# SCH_555-Circuit_2025-12-31.net
KiCad netlist of a schematic drawn in EasyEDA
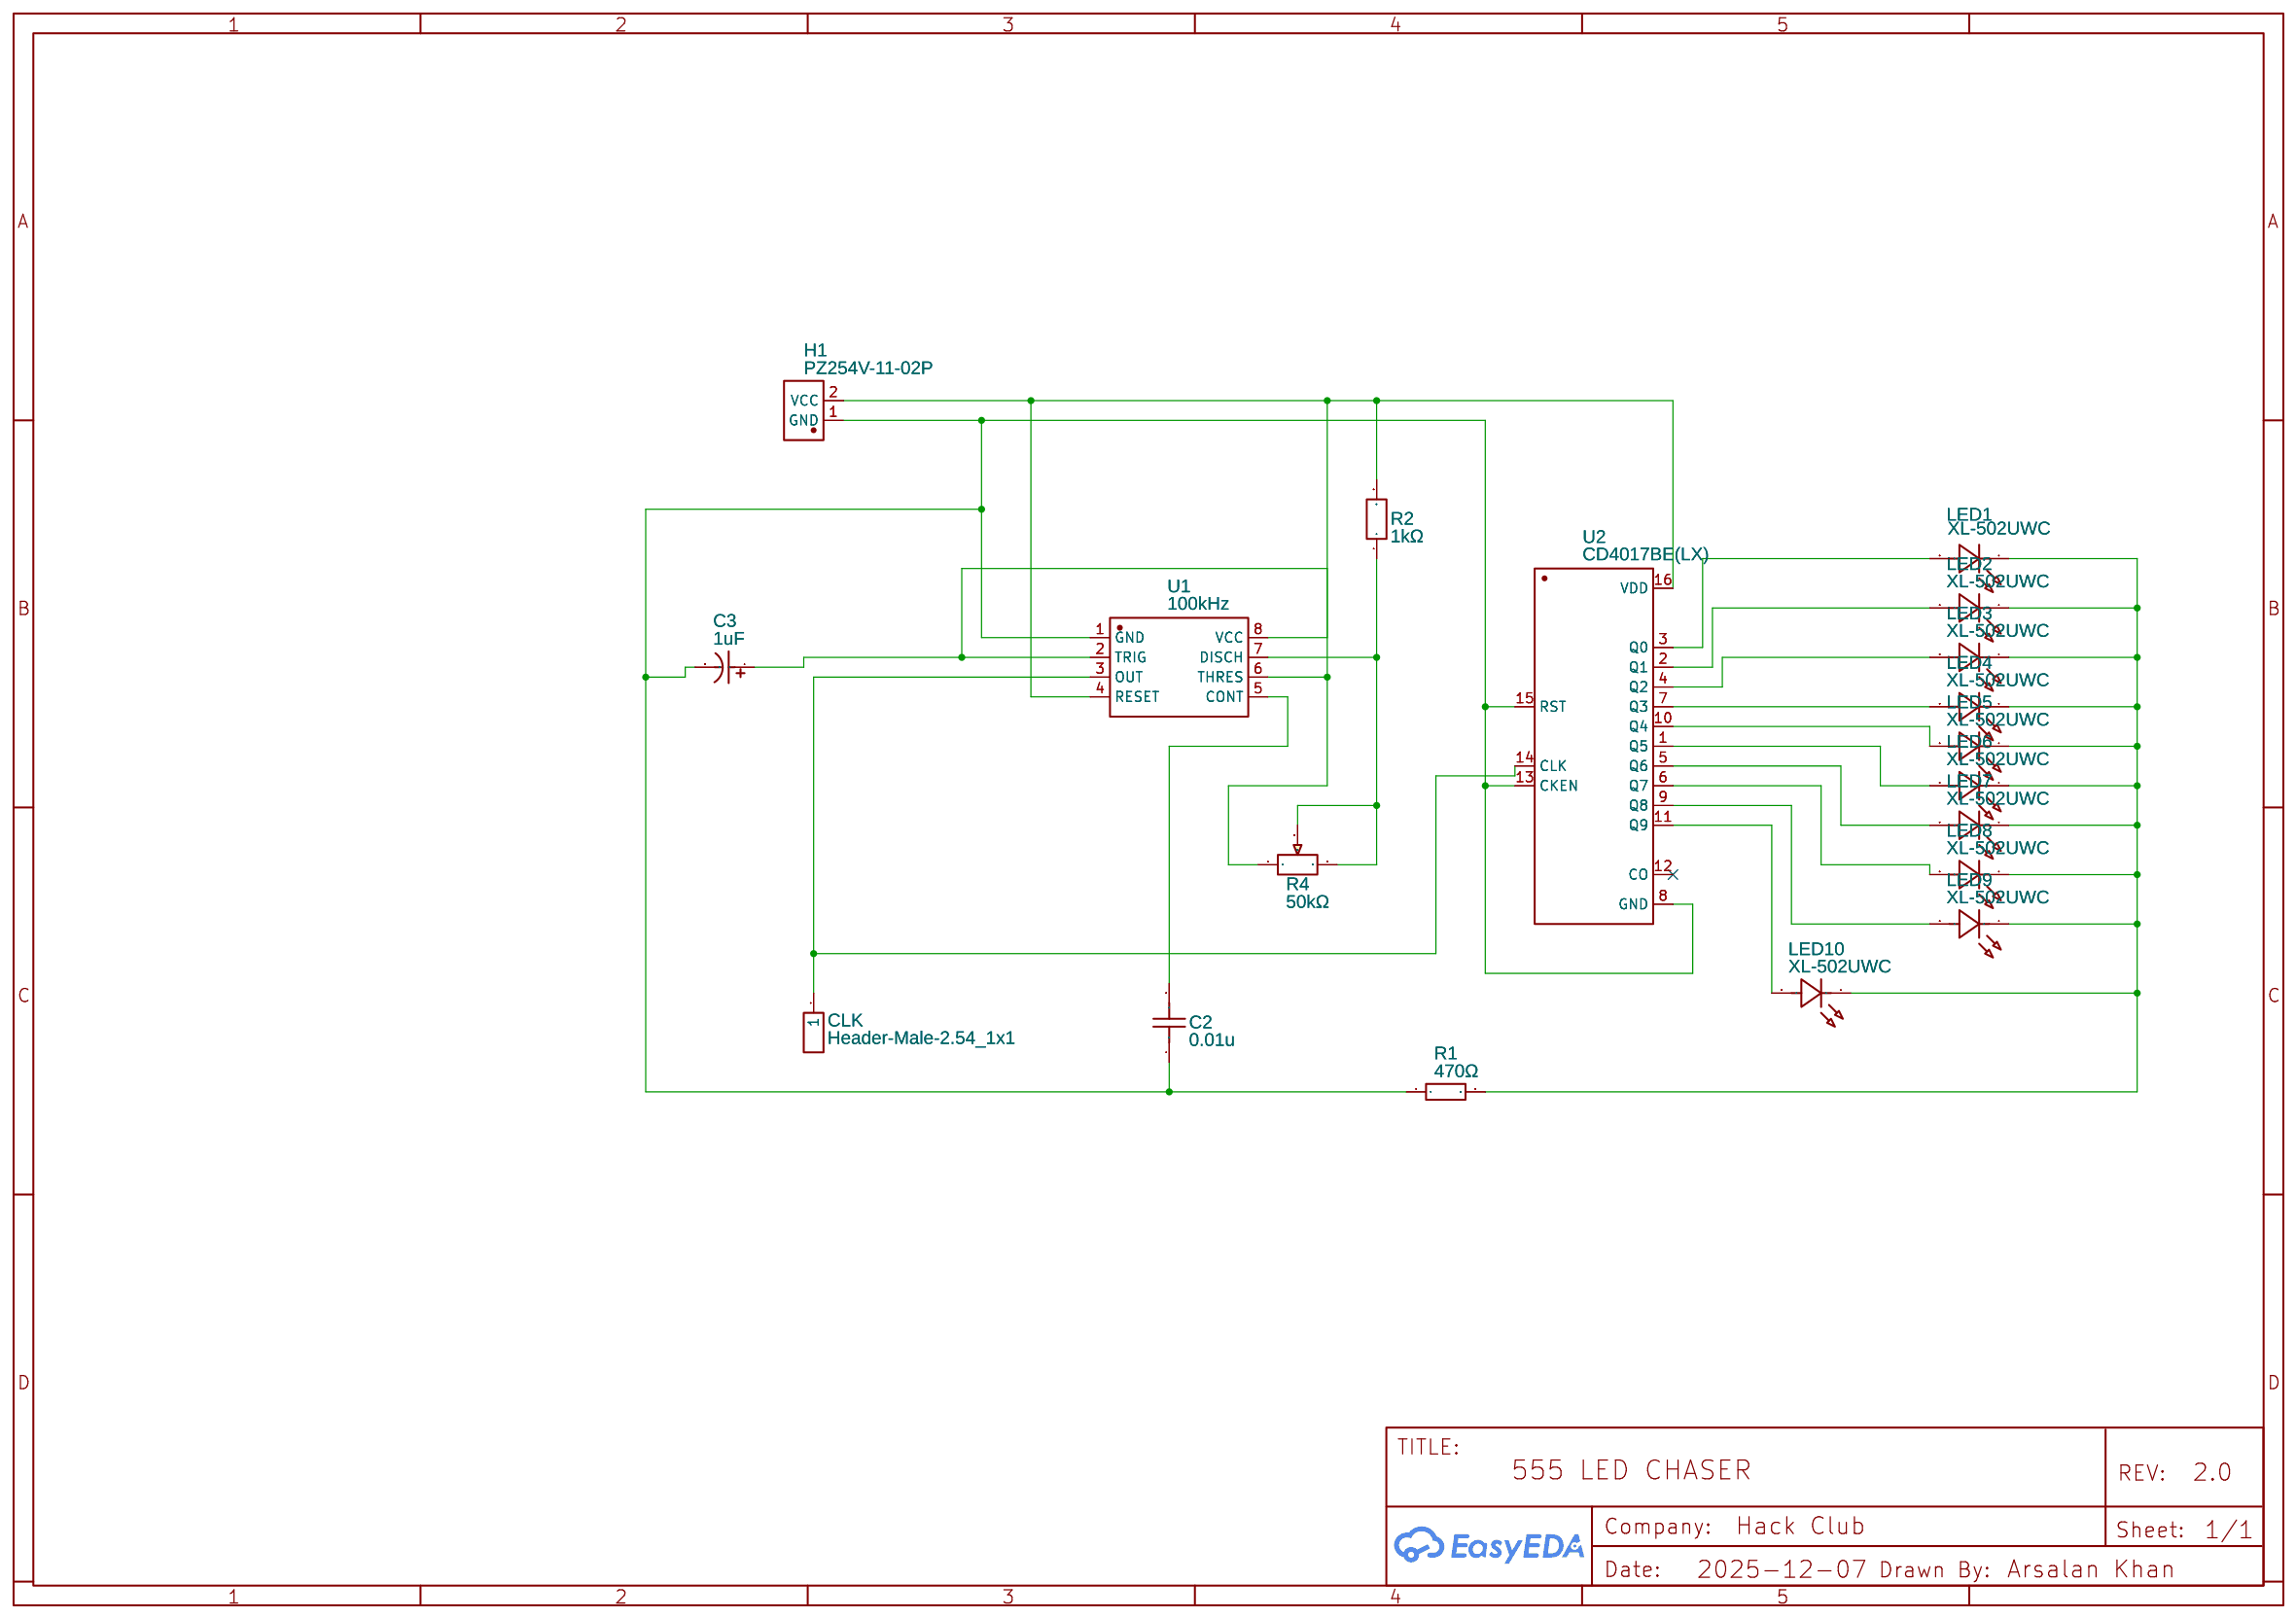
[diagram p0: schematic sheet]

(export (version "E")
  (design (tool "Eeschema 10.0.6"))
  (components
    (comp (ref "C2")
      (value "0.01u")
      (fields (field (name "Manufacturer Part") "N09F1B103MN0B0S0N0") (field (name "Manufacturer") "STE(松田)"))
      (libsource (lib "") (part "N09F1B103MN0B0S0N0"))
    )
    (comp (ref "C3")
      (value "1uF")
      (fields (field (name "Manufacturer Part") "KF010M050C110A") (field (name "Manufacturer") "CapXon(丰宾)"))
      (libsource (lib "") (part "KF010M050C110A"))
    )
    (comp (ref "CLK")
      (value "Header-Male-2.54_1x1")
      (fields (field (name "Manufacturer Part") "2.54-1*1P针") (field (name "Manufacturer") "BOOMELE(博穆精密)"))
      (libsource (lib "") (part "Header-Male-2.54_1x1"))
    )
    (comp (ref "H1")
      (value "PZ254V-11-02P")
      (fields (field (name "Manufacturer") "XFCN(兴飞)"))
      (libsource (lib "") (part "PZ254V-11-02P"))
    )
    (comp (ref "LED1")
      (value "XL-502UWC")
      (fields (field (name "Manufacturer") "XINGLIGHT(成兴光)"))
      (libsource (lib "") (part "XL-502UWC"))
    )
    (comp (ref "LED2")
      (value "XL-502UWC")
      (fields (field (name "Manufacturer") "XINGLIGHT(成兴光)"))
      (libsource (lib "") (part "XL-502UWC"))
    )
    (comp (ref "LED3")
      (value "XL-502UWC")
      (fields (field (name "Manufacturer") "XINGLIGHT(成兴光)"))
      (libsource (lib "") (part "XL-502UWC"))
    )
    (comp (ref "LED4")
      (value "XL-502UWC")
      (fields (field (name "Manufacturer") "XINGLIGHT(成兴光)"))
      (libsource (lib "") (part "XL-502UWC"))
    )
    (comp (ref "LED5")
      (value "XL-502UWC")
      (fields (field (name "Manufacturer") "XINGLIGHT(成兴光)"))
      (libsource (lib "") (part "XL-502UWC"))
    )
    (comp (ref "LED6")
      (value "XL-502UWC")
      (fields (field (name "Manufacturer") "XINGLIGHT(成兴光)"))
      (libsource (lib "") (part "XL-502UWC"))
    )
    (comp (ref "LED7")
      (value "XL-502UWC")
      (fields (field (name "Manufacturer") "XINGLIGHT(成兴光)"))
      (libsource (lib "") (part "XL-502UWC"))
    )
    (comp (ref "LED8")
      (value "XL-502UWC")
      (fields (field (name "Manufacturer") "XINGLIGHT(成兴光)"))
      (libsource (lib "") (part "XL-502UWC"))
    )
    (comp (ref "LED9")
      (value "XL-502UWC")
      (fields (field (name "Manufacturer") "XINGLIGHT(成兴光)"))
      (libsource (lib "") (part "XL-502UWC"))
    )
    (comp (ref "LED10")
      (value "XL-502UWC")
      (fields (field (name "Manufacturer") "XINGLIGHT(成兴光)"))
      (libsource (lib "") (part "XL-502UWC"))
    )
    (comp (ref "R1")
      (value "470Ω")
      (fields
        (field (name "Manufacturer Part") "MFR0W4F4700A50")
        (field (name "Manufacturer") "UNI-ROYAL(厚声)")
      )
      (libsource (lib "") (part "MFR0W4F4700A50"))
    )
    (comp (ref "R2")
      (value "1kΩ")
      (fields (field (name "Manufacturer Part") "MF1/4W-1KΩ±1%T52") (field (name "Manufacturer") "华星机电"))
      (libsource (lib "") (part "MF1/4W-1KΩ±1%T52"))
    )
    (comp (ref "R4")
      (value "50kΩ")
      (fields (field (name "Manufacturer Part") "3296X-1-503") (field (name "Manufacturer") "BOCHEN(博晨)"))
      (libsource (lib "") (part "3296X-1-503_C118912"))
    )
    (comp (ref "U1")
      (value "100kHz")
      (fields (field (name "Manufacturer Part") "NE555P") (field (name "Manufacturer") "TI(德州仪器)"))
      (libsource (lib "") (part "NE555P"))
    )
    (comp (ref "U2")
      (value "CD4017BE(LX)")
      (fields (field (name "Manufacturer") "LX(灵星芯微)"))
      (libsource (lib "") (part "CD4017BE(LX)"))
    )
  )
  (nets
    (net (code "1") (name "Net-(H1-GND)") (class "Default")
      (node (ref "C2") (pin "1") (pinfunction "1_1") (pintype "unspecified"))
      (node (ref "C3") (pin "2") (pinfunction "2_2") (pintype "input"))
      (node (ref "H1") (pin "1") (pinfunction "GND_1") (pintype "unspecified"))
      (node (ref "R1") (pin "1") (pinfunction "1_1") (pintype "input"))
      (node (ref "U1") (pin "1") (pinfunction "GND_1") (pintype "unspecified"))
      (node (ref "U2") (pin "13") (pinfunction "CKEN_13") (pintype "unspecified"))
      (node (ref "U2") (pin "15") (pinfunction "RST_15") (pintype "unspecified"))
      (node (ref "U2") (pin "8") (pinfunction "GND_8") (pintype "unspecified"))
    )
    (net (code "2") (name "Net-(H1-VCC)") (class "Default")
      (node (ref "H1") (pin "2") (pinfunction "VCC_2") (pintype "unspecified"))
      (node (ref "R2") (pin "2") (pinfunction "2_2") (pintype "unspecified"))
      (node (ref "U1") (pin "4") (pinfunction "RESET_4") (pintype "unspecified"))
      (node (ref "U1") (pin "8") (pinfunction "VCC_8") (pintype "unspecified"))
      (node (ref "U2") (pin "16") (pinfunction "VDD_16") (pintype "unspecified"))
    )
    (net (code "3") (name "Net-(LED1-A)") (class "Default")
      (node (ref "LED1") (pin "2") (pinfunction "A_2") (pintype "unspecified"))
      (node (ref "U2") (pin "3") (pinfunction "Q0_3") (pintype "unspecified"))
    )
    (net (code "4") (name "Net-(LED1-K)") (class "Default")
      (node (ref "LED1") (pin "1") (pinfunction "K_1") (pintype "unspecified"))
      (node (ref "LED10") (pin "1") (pinfunction "K_1") (pintype "unspecified"))
      (node (ref "LED2") (pin "1") (pinfunction "K_1") (pintype "unspecified"))
      (node (ref "LED3") (pin "1") (pinfunction "K_1") (pintype "unspecified"))
      (node (ref "LED4") (pin "1") (pinfunction "K_1") (pintype "unspecified"))
      (node (ref "LED5") (pin "1") (pinfunction "K_1") (pintype "unspecified"))
      (node (ref "LED6") (pin "1") (pinfunction "K_1") (pintype "unspecified"))
      (node (ref "LED7") (pin "1") (pinfunction "K_1") (pintype "unspecified"))
      (node (ref "LED8") (pin "1") (pinfunction "K_1") (pintype "unspecified"))
      (node (ref "LED9") (pin "1") (pinfunction "K_1") (pintype "unspecified"))
      (node (ref "R1") (pin "2") (pinfunction "2_2") (pintype "input"))
    )
    (net (code "5") (name "Net-(LED2-A)") (class "Default")
      (node (ref "LED2") (pin "2") (pinfunction "A_2") (pintype "unspecified"))
      (node (ref "U2") (pin "2") (pinfunction "Q1_2") (pintype "unspecified"))
    )
    (net (code "6") (name "Net-(LED3-A)") (class "Default")
      (node (ref "LED3") (pin "2") (pinfunction "A_2") (pintype "unspecified"))
      (node (ref "U2") (pin "4") (pinfunction "Q2_4") (pintype "unspecified"))
    )
    (net (code "7") (name "Net-(LED4-A)") (class "Default")
      (node (ref "LED4") (pin "2") (pinfunction "A_2") (pintype "unspecified"))
      (node (ref "U2") (pin "7") (pinfunction "Q3_7") (pintype "unspecified"))
    )
    (net (code "8") (name "Net-(LED5-A)") (class "Default")
      (node (ref "LED5") (pin "2") (pinfunction "A_2") (pintype "unspecified"))
      (node (ref "U2") (pin "10") (pinfunction "Q4_10") (pintype "unspecified"))
    )
    (net (code "9") (name "Net-(LED6-A)") (class "Default")
      (node (ref "LED6") (pin "2") (pinfunction "A_2") (pintype "unspecified"))
      (node (ref "U2") (pin "1") (pinfunction "Q5_1") (pintype "unspecified"))
    )
    (net (code "10") (name "Net-(LED7-A)") (class "Default")
      (node (ref "LED7") (pin "2") (pinfunction "A_2") (pintype "unspecified"))
      (node (ref "U2") (pin "5") (pinfunction "Q6_5") (pintype "unspecified"))
    )
    (net (code "11") (name "Net-(LED8-A)") (class "Default")
      (node (ref "LED8") (pin "2") (pinfunction "A_2") (pintype "unspecified"))
      (node (ref "U2") (pin "6") (pinfunction "Q7_6") (pintype "unspecified"))
    )
    (net (code "12") (name "Net-(LED9-A)") (class "Default")
      (node (ref "LED9") (pin "2") (pinfunction "A_2") (pintype "unspecified"))
      (node (ref "U2") (pin "9") (pinfunction "Q8_9") (pintype "unspecified"))
    )
    (net (code "13") (name "Net-(LED10-A)") (class "Default")
      (node (ref "LED10") (pin "2") (pinfunction "A_2") (pintype "unspecified"))
      (node (ref "U2") (pin "11") (pinfunction "Q9_11") (pintype "unspecified"))
    )
    (net (code "14") (name "Net-(U1-CONT)") (class "Default")
      (node (ref "C2") (pin "2") (pinfunction "2_2") (pintype "unspecified"))
      (node (ref "U1") (pin "5") (pinfunction "CONT_5") (pintype "unspecified"))
    )
    (net (code "15") (name "Net-(U1-DISCH)") (class "Default")
      (node (ref "R2") (pin "1") (pinfunction "1_1") (pintype "unspecified"))
      (node (ref "R4") (pin "2") (pinfunction "2_2") (pintype "input"))
      (node (ref "R4") (pin "3") (pinfunction "3_3") (pintype "input"))
      (node (ref "U1") (pin "7") (pinfunction "DISCH_7") (pintype "unspecified"))
    )
    (net (code "16") (name "Net-(U1-OUT)") (class "Default")
      (node (ref "CLK") (pin "1") (pinfunction "1_1") (pintype "input"))
      (node (ref "U1") (pin "3") (pinfunction "OUT_3") (pintype "unspecified"))
      (node (ref "U2") (pin "14") (pinfunction "CLK_14") (pintype "unspecified"))
    )
    (net (code "17") (name "Net-(U1-THRES)") (class "Default")
      (node (ref "C3") (pin "1") (pinfunction "1_1") (pintype "input"))
      (node (ref "R4") (pin "1") (pinfunction "1_1") (pintype "input"))
      (node (ref "U1") (pin "2") (pinfunction "TRIG_2") (pintype "unspecified"))
      (node (ref "U1") (pin "6") (pinfunction "THRES_6") (pintype "unspecified"))
    )
    (net (code "18") (name "unconnected-(U2-CO-Pad12)") (class "Default")
      (node (ref "U2") (pin "12") (pinfunction "CO_12") (pintype "unspecified+no_connect"))
    )
  )
)
